# project_pankov_1_power_supply.net
KiCad netlist of a schematic drawn in Altium Designer
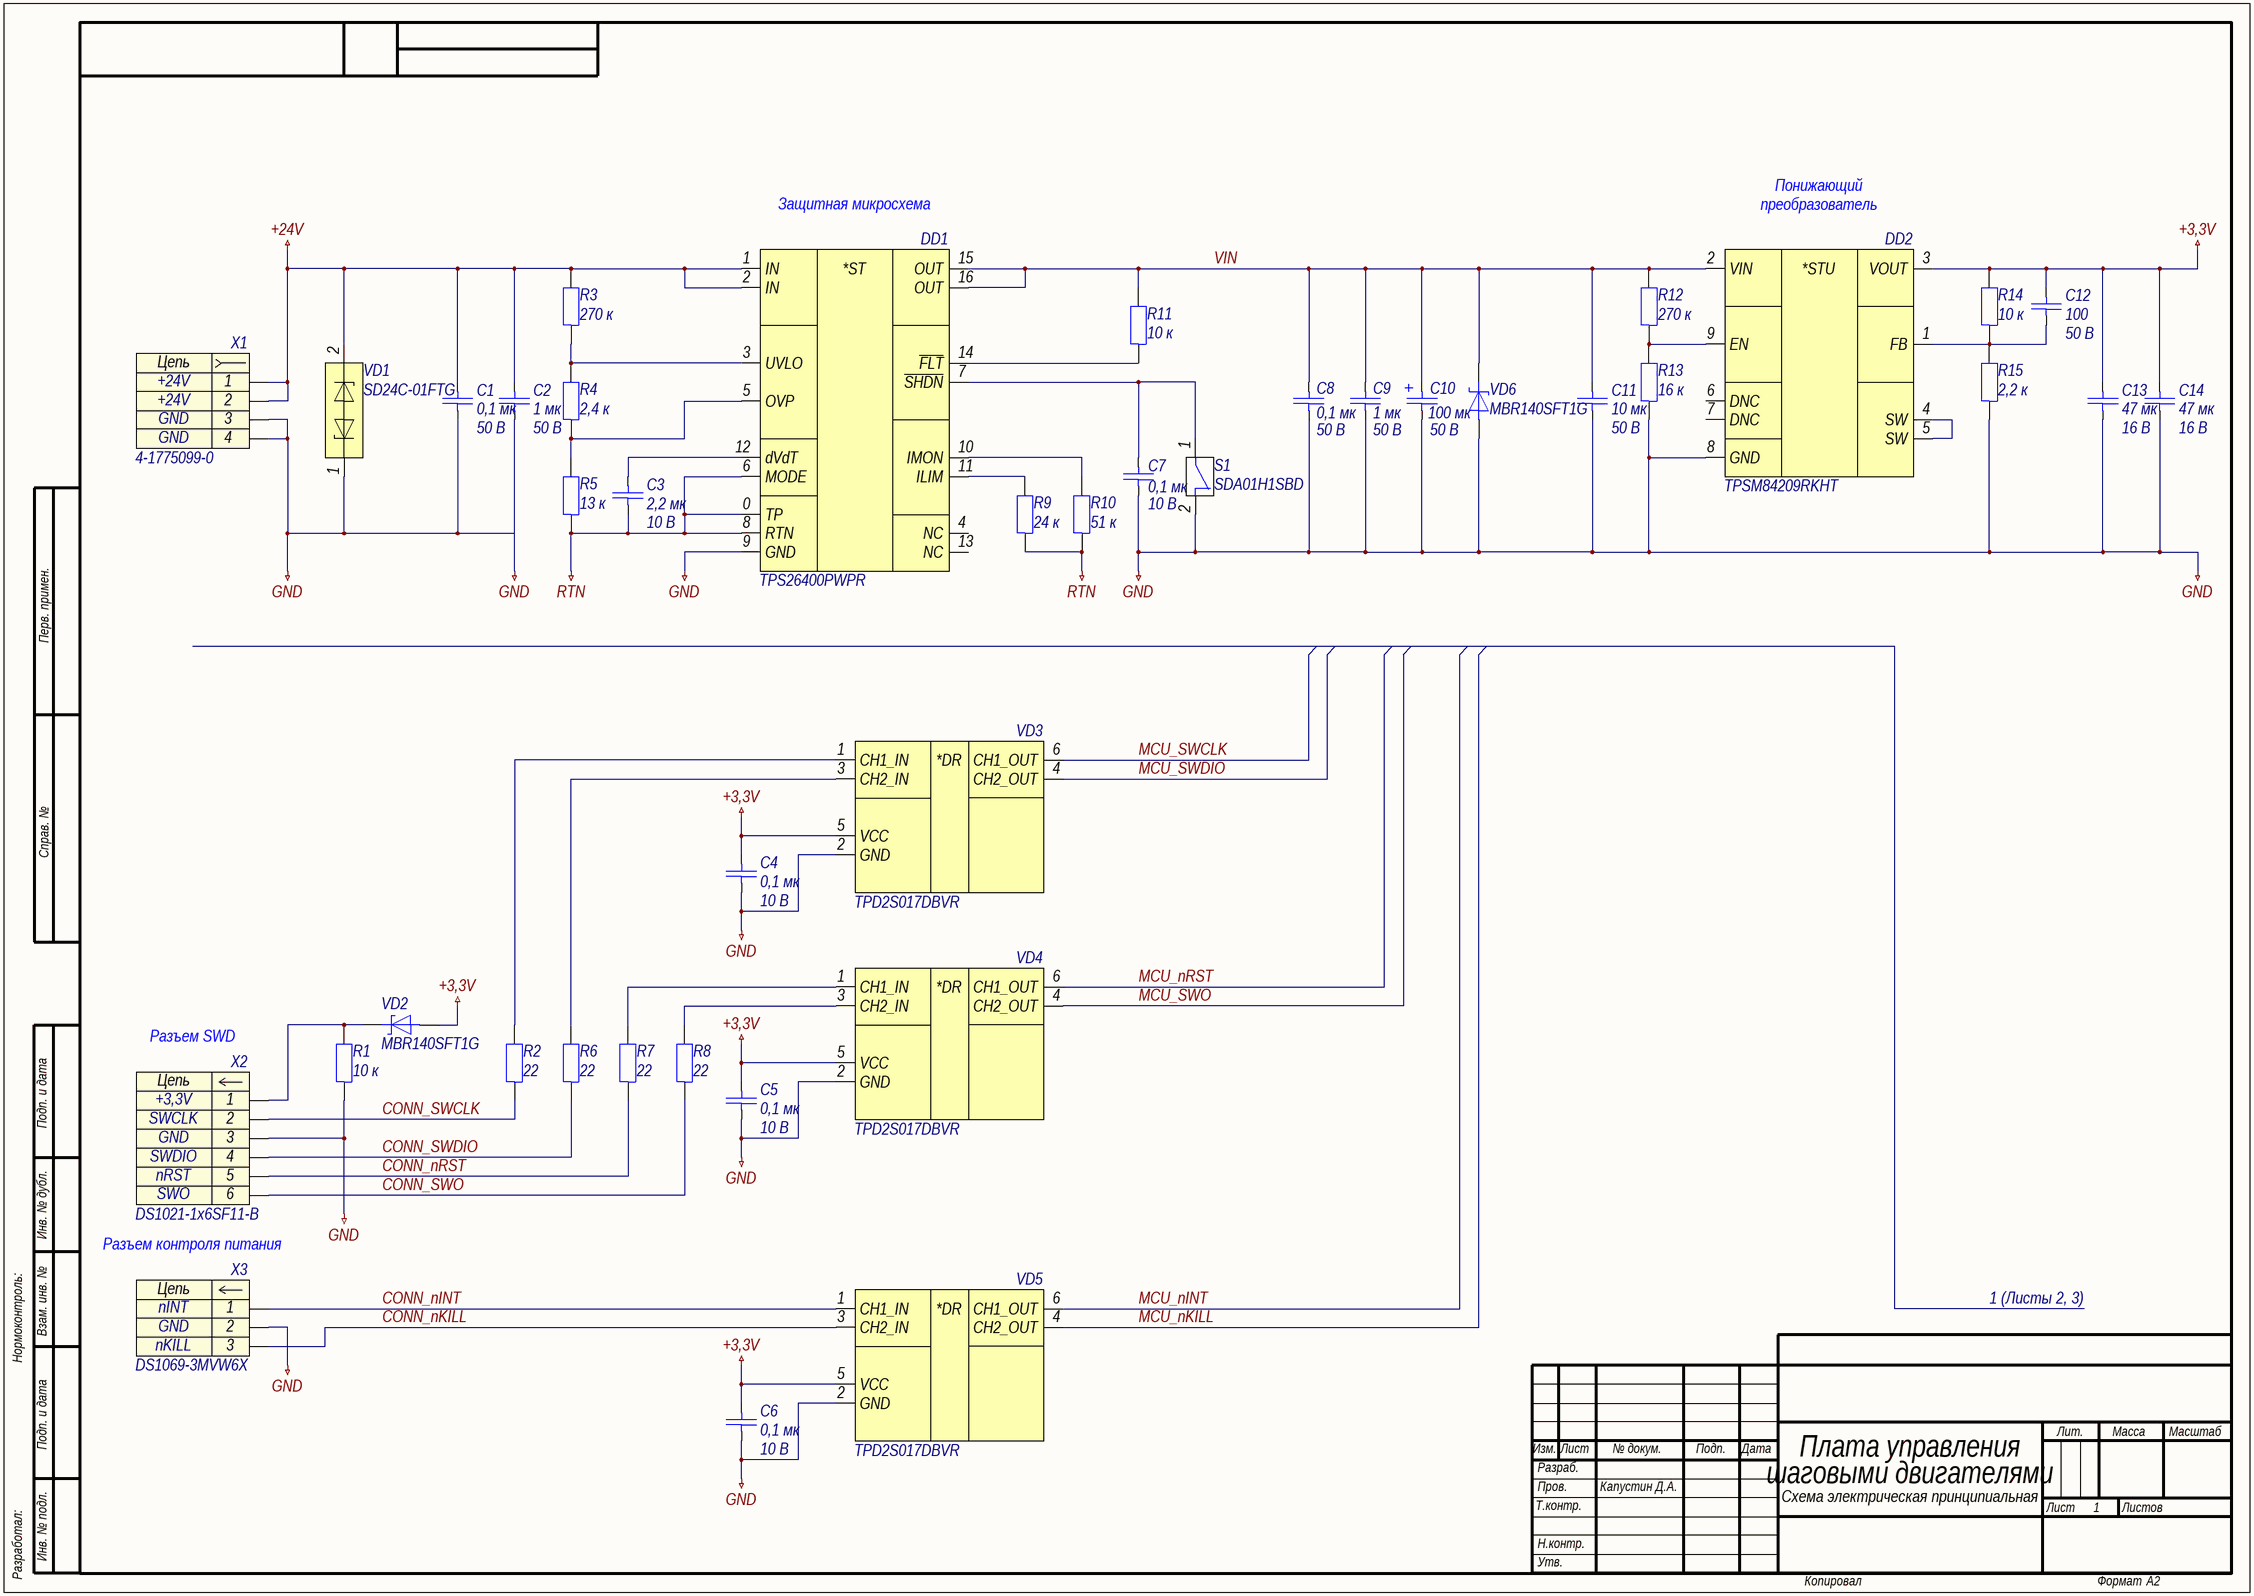
[diagram p0: project_pankov_1_power_supply.SchDoc]

(export (version "E")
  (design (tool "Eeschema 10.0.6"))
  (components
    (comp (ref "C1")
      (value "0,1 мк")
      (footprint "C0603")
      (description "=Описание")
      (fields (field (name "НАПРЯЖЕНИЕ") "50 В"))
      (libsource (lib "Database_Students") (part "CAPACITOR-NONPOLAR"))
    )
    (comp (ref "C2")
      (value "1 мк")
      (footprint "C0603")
      (description "=Описание")
      (fields (field (name "НАПРЯЖЕНИЕ") "50 В"))
      (libsource (lib "Database_Students") (part "CAPACITOR-NONPOLAR"))
    )
    (comp (ref "C3")
      (value "2,2 мк")
      (footprint "C0603")
      (description "=Описание")
      (fields (field (name "НАПРЯЖЕНИЕ") "10 В"))
      (libsource (lib "Database_Students") (part "CAPACITOR-NONPOLAR"))
    )
    (comp (ref "C4")
      (value "0,1 мк")
      (footprint "C0603")
      (description "=Описание")
      (fields (field (name "НАПРЯЖЕНИЕ") "10 В"))
      (libsource (lib "Database_Students") (part "CAPACITOR-NONPOLAR"))
    )
    (comp (ref "C5")
      (value "0,1 мк")
      (footprint "C0603")
      (description "=Описание")
      (fields (field (name "НАПРЯЖЕНИЕ") "10 В"))
      (libsource (lib "Database_Students") (part "CAPACITOR-NONPOLAR"))
    )
    (comp (ref "C6")
      (value "0,1 мк")
      (footprint "C0603")
      (description "=Описание")
      (fields (field (name "НАПРЯЖЕНИЕ") "10 В"))
      (libsource (lib "Database_Students") (part "CAPACITOR-NONPOLAR"))
    )
    (comp (ref "C7")
      (value "0,1 мк")
      (footprint "C0603")
      (description "=Описание")
      (fields (field (name "НАПРЯЖЕНИЕ") "10 В"))
      (libsource (lib "Database_Students") (part "CAPACITOR-NONPOLAR"))
    )
    (comp (ref "C8")
      (value "0,1 мк")
      (footprint "C0603")
      (description "=Описание")
      (fields (field (name "НАПРЯЖЕНИЕ") "50 В"))
      (libsource (lib "Database_Students") (part "CAPACITOR-NONPOLAR"))
    )
    (comp (ref "C9")
      (value "1 мк")
      (footprint "C0603")
      (description "=Описание")
      (fields (field (name "НАПРЯЖЕНИЕ") "50 В"))
      (libsource (lib "Database_Students") (part "CAPACITOR-NONPOLAR"))
    )
    (comp (ref "C10")
      (value "100 мк")
      (footprint "CAPAE-660X660X800")
      (description "=Описание")
      (fields (field (name "НАПРЯЖЕНИЕ") "50 В"))
      (libsource (lib "Database_Students") (part "CAPACITOR-POLAR"))
    )
    (comp (ref "C11")
      (value "10 мк")
      (footprint "C1206")
      (description "=Описание")
      (fields (field (name "НАПРЯЖЕНИЕ") "50 В"))
      (libsource (lib "Database_Students") (part "CAPACITOR-NONPOLAR"))
    )
    (comp (ref "C12")
      (value "100")
      (footprint "C0603")
      (description "=Описание")
      (fields (field (name "НАПРЯЖЕНИЕ") "50 В"))
      (libsource (lib "Database_Students") (part "CAPACITOR-NONPOLAR"))
    )
    (comp (ref "C13")
      (value "47 мк")
      (footprint "C1206")
      (description "=Описание")
      (fields (field (name "НАПРЯЖЕНИЕ") "16 В"))
      (libsource (lib "Database_Students") (part "CAPACITOR-NONPOLAR"))
    )
    (comp (ref "C14")
      (value "47 мк")
      (footprint "C1206")
      (description "=Описание")
      (fields (field (name "НАПРЯЖЕНИЕ") "16 В"))
      (libsource (lib "Database_Students") (part "CAPACITOR-NONPOLAR"))
    )
    (comp (ref "DD1")
      (value "TPS26400PWPR")
      (footprint "HTSSOP-16-P65-500X440X120-L63X25-T246X266")
      (description "=Описание")
      (libsource (lib "Database_Students") (part "TPS26400PWPR"))
    )
    (comp (ref "DD2")
      (value "TPSM84209RKHT")
      (footprint "QFN-FCMOD-9-P65-450X400X210")
      (description "=Описание")
      (libsource (lib "Database_Students") (part "TPSM84209RKHT"))
    )
    (comp (ref "R1")
      (value "10 к")
      (footprint "R0603")
      (description "=Описание")
      (libsource (lib "Database_Students") (part "RESISTOR-COMMON"))
    )
    (comp (ref "R2")
      (value "22")
      (footprint "R0603")
      (description "=Описание")
      (libsource (lib "Database_Students") (part "RESISTOR-COMMON"))
    )
    (comp (ref "R3")
      (value "270 к")
      (footprint "R0603")
      (description "=Описание")
      (libsource (lib "Database_Students") (part "RESISTOR-COMMON"))
    )
    (comp (ref "R4")
      (value "2,4 к")
      (footprint "R0603")
      (description "=Описание")
      (libsource (lib "Database_Students") (part "RESISTOR-COMMON"))
    )
    (comp (ref "R5")
      (value "13 к")
      (footprint "R0603")
      (description "=Описание")
      (libsource (lib "Database_Students") (part "RESISTOR-COMMON"))
    )
    (comp (ref "R6")
      (value "22")
      (footprint "R0603")
      (description "=Описание")
      (libsource (lib "Database_Students") (part "RESISTOR-COMMON"))
    )
    (comp (ref "R7")
      (value "22")
      (footprint "R0603")
      (description "=Описание")
      (libsource (lib "Database_Students") (part "RESISTOR-COMMON"))
    )
    (comp (ref "R8")
      (value "22")
      (footprint "R0603")
      (description "=Описание")
      (libsource (lib "Database_Students") (part "RESISTOR-COMMON"))
    )
    (comp (ref "R9")
      (value "24 к")
      (footprint "R0603")
      (description "=Описание")
      (libsource (lib "Database_Students") (part "RESISTOR-COMMON"))
    )
    (comp (ref "R10")
      (value "51 к")
      (footprint "R0603")
      (description "=Описание")
      (libsource (lib "Database_Students") (part "RESISTOR-COMMON"))
    )
    (comp (ref "R11")
      (value "10 к")
      (footprint "R0603")
      (description "=Описание")
      (libsource (lib "Database_Students") (part "RESISTOR-COMMON"))
    )
    (comp (ref "R12")
      (value "270 к")
      (footprint "R0603")
      (description "=Описание")
      (libsource (lib "Database_Students") (part "RESISTOR-COMMON"))
    )
    (comp (ref "R13")
      (value "16 к")
      (footprint "R0603")
      (description "=Описание")
      (libsource (lib "Database_Students") (part "RESISTOR-COMMON"))
    )
    (comp (ref "R14")
      (value "10 к")
      (footprint "R0603")
      (description "=Описание")
      (libsource (lib "Database_Students") (part "RESISTOR-COMMON"))
    )
    (comp (ref "R15")
      (value "2,2 к")
      (footprint "R0603")
      (description "=Описание")
      (libsource (lib "Database_Students") (part "RESISTOR-COMMON"))
    )
    (comp (ref "S1")
      (value "SDA01H1SBD")
      (footprint "SDA01H1SBD")
      (description "=Описание")
      (libsource (lib "Database_Students") (part "SWITCH-2C"))
    )
    (comp (ref "VD1")
      (value "SD24C-01FTG")
      (footprint "SOD-323-257X130X114")
      (description "=Описание")
      (libsource (lib "Database_Students") (part "ZENER-BI-DIRECTIONAL"))
    )
    (comp (ref "VD2")
      (value "MBR140SFT1G")
      (footprint "SOD-123FL-370X165X98")
      (description "=Описание")
      (libsource (lib "Database_Students") (part "DIODE-SCHOTTKY"))
    )
    (comp (ref "VD3")
      (value "TPD2S017DBVR")
      (footprint "SOT-23-6-P95-290X280X145")
      (description "=Описание")
      (libsource (lib "Database_Students") (part "TPD2S017DBVR"))
    )
    (comp (ref "VD4")
      (value "TPD2S017DBVR")
      (footprint "SOT-23-6-P95-290X280X145")
      (description "=Описание")
      (libsource (lib "Database_Students") (part "TPD2S017DBVR"))
    )
    (comp (ref "VD5")
      (value "TPD2S017DBVR")
      (footprint "SOT-23-6-P95-290X280X145")
      (description "=Описание")
      (libsource (lib "Database_Students") (part "TPD2S017DBVR"))
    )
    (comp (ref "VD6")
      (value "MBR140SFT1G")
      (footprint "SOD-123FL-370X165X98")
      (description "=Описание")
      (libsource (lib "Database_Students") (part "DIODE-SCHOTTKY"))
    )
    (comp (ref "X1")
      (value "4-1775099-0")
      (footprint "4-1775099-0")
      (description "=Описание")
      (libsource (lib "Database_Students") (part "HEADER-4-SCT"))
    )
    (comp (ref "X2")
      (value "DS1021-1x6SF11-B")
      (footprint "DS1021-1X6SF11-B")
      (description "=Описание")
      (libsource (lib "Database_Students") (part "HEADER-6-PLG"))
    )
    (comp (ref "X3")
      (value "DS1069-3MVW6X")
      (footprint "DS1069-3MVW6X")
      (description "=Описание")
      (libsource (lib "Database_Students") (part "HEADER-3-PLG"))
    )
  )
  (nets
    (net (code "1") (name "+3,3V") (class "Default")
      (node (ref "C12") (pin "1") (pinfunction "1_1") (pintype "passive"))
      (node (ref "C13") (pin "1") (pinfunction "1_1") (pintype "passive"))
      (node (ref "C14") (pin "1") (pinfunction "1_1") (pintype "passive"))
      (node (ref "C4") (pin "1") (pinfunction "1_1") (pintype "passive"))
      (node (ref "C5") (pin "1") (pinfunction "1_1") (pintype "passive"))
      (node (ref "C6") (pin "1") (pinfunction "1_1") (pintype "passive"))
      (node (ref "DD2") (pin "3") (pinfunction "VOUT_3") (pintype "passive"))
      (node (ref "R14") (pin "2") (pinfunction "2_2") (pintype "passive"))
      (node (ref "VD2") (pin "2") (pinfunction "2_2") (pintype "passive"))
      (node (ref "VD3") (pin "5") (pinfunction "VCC_5") (pintype "passive"))
      (node (ref "VD4") (pin "5") (pinfunction "VCC_5") (pintype "passive"))
      (node (ref "VD5") (pin "5") (pinfunction "VCC_5") (pintype "passive"))
    )
    (net (code "2") (name "+24V") (class "Default")
      (node (ref "C1") (pin "1") (pinfunction "1_1") (pintype "passive"))
      (node (ref "C2") (pin "1") (pinfunction "1_1") (pintype "passive"))
      (node (ref "DD1") (pin "1") (pinfunction "IN_1") (pintype "passive"))
      (node (ref "DD1") (pin "2") (pinfunction "IN_2") (pintype "passive"))
      (node (ref "R3") (pin "2") (pinfunction "2_2") (pintype "passive"))
      (node (ref "VD1") (pin "2") (pinfunction "2_2") (pintype "passive"))
      (node (ref "X1") (pin "1") (pinfunction "1_1") (pintype "passive"))
      (node (ref "X1") (pin "2") (pinfunction "2_2") (pintype "passive"))
    )
    (net (code "3") (name "/CONN_SWCLK") (class "Default")
      (node (ref "R2") (pin "1") (pinfunction "1_1") (pintype "passive"))
      (node (ref "X2") (pin "2") (pinfunction "2_2") (pintype "passive"))
    )
    (net (code "4") (name "/CONN_SWDIO") (class "Default")
      (node (ref "R6") (pin "1") (pinfunction "1_1") (pintype "passive"))
      (node (ref "X2") (pin "4") (pinfunction "4_4") (pintype "passive"))
    )
    (net (code "5") (name "/CONN_SWO") (class "Default")
      (node (ref "R8") (pin "1") (pinfunction "1_1") (pintype "passive"))
      (node (ref "X2") (pin "6") (pinfunction "6_6") (pintype "passive"))
    )
    (net (code "6") (name "/CONN_nINT") (class "Default")
      (node (ref "VD5") (pin "1") (pinfunction "CH1_IN_1") (pintype "passive"))
      (node (ref "X3") (pin "1") (pinfunction "1_1") (pintype "passive"))
    )
    (net (code "7") (name "/CONN_nKILL") (class "Default")
      (node (ref "VD5") (pin "3") (pinfunction "CH2_IN_3") (pintype "passive"))
      (node (ref "X3") (pin "3") (pinfunction "3_3") (pintype "passive"))
    )
    (net (code "8") (name "/CONN_nRST") (class "Default")
      (node (ref "R7") (pin "1") (pinfunction "1_1") (pintype "passive"))
      (node (ref "X2") (pin "5") (pinfunction "5_5") (pintype "passive"))
    )
    (net (code "9") (name "/MCU_SWCLK") (class "Default")
      (node (ref "VD3") (pin "6") (pinfunction "CH1_OUT_6") (pintype "passive"))
    )
    (net (code "10") (name "/MCU_SWDIO") (class "Default")
      (node (ref "VD3") (pin "4") (pinfunction "CH2_OUT_4") (pintype "passive"))
    )
    (net (code "11") (name "/MCU_SWO") (class "Default")
      (node (ref "VD4") (pin "4") (pinfunction "CH2_OUT_4") (pintype "passive"))
    )
    (net (code "12") (name "/MCU_nINT") (class "Default")
      (node (ref "VD5") (pin "6") (pinfunction "CH1_OUT_6") (pintype "passive"))
    )
    (net (code "13") (name "/MCU_nKILL") (class "Default")
      (node (ref "VD5") (pin "4") (pinfunction "CH2_OUT_4") (pintype "passive"))
    )
    (net (code "14") (name "/MCU_nRST") (class "Default")
      (node (ref "VD4") (pin "6") (pinfunction "CH1_OUT_6") (pintype "passive"))
    )
    (net (code "15") (name "/VIN") (class "Default")
      (node (ref "C10") (pin "1") (pinfunction "1_1") (pintype "passive"))
      (node (ref "C11") (pin "1") (pinfunction "1_1") (pintype "passive"))
      (node (ref "C8") (pin "1") (pinfunction "1_1") (pintype "passive"))
      (node (ref "C9") (pin "1") (pinfunction "1_1") (pintype "passive"))
      (node (ref "DD1") (pin "15") (pinfunction "OUT_15") (pintype "passive"))
      (node (ref "DD1") (pin "16") (pinfunction "OUT_16") (pintype "passive"))
      (node (ref "DD2") (pin "2") (pinfunction "VIN_2") (pintype "passive"))
      (node (ref "R11") (pin "2") (pinfunction "2_2") (pintype "passive"))
      (node (ref "R12") (pin "2") (pinfunction "2_2") (pintype "passive"))
      (node (ref "VD6") (pin "1") (pinfunction "1_1") (pintype "passive"))
    )
    (net (code "16") (name "GND") (class "Default")
      (node (ref "C1") (pin "2") (pinfunction "2_2") (pintype "passive"))
      (node (ref "C10") (pin "2") (pinfunction "2_2") (pintype "passive"))
      (node (ref "C11") (pin "2") (pinfunction "2_2") (pintype "passive"))
      (node (ref "C13") (pin "2") (pinfunction "2_2") (pintype "passive"))
      (node (ref "C14") (pin "2") (pinfunction "2_2") (pintype "passive"))
      (node (ref "C2") (pin "2") (pinfunction "2_2") (pintype "passive"))
      (node (ref "C4") (pin "2") (pinfunction "2_2") (pintype "passive"))
      (node (ref "C5") (pin "2") (pinfunction "2_2") (pintype "passive"))
      (node (ref "C6") (pin "2") (pinfunction "2_2") (pintype "passive"))
      (node (ref "C7") (pin "2") (pinfunction "2_2") (pintype "passive"))
      (node (ref "C8") (pin "2") (pinfunction "2_2") (pintype "passive"))
      (node (ref "C9") (pin "2") (pinfunction "2_2") (pintype "passive"))
      (node (ref "DD1") (pin "9") (pinfunction "GND_9") (pintype "passive"))
      (node (ref "DD2") (pin "8") (pinfunction "GND_8") (pintype "passive"))
      (node (ref "R1") (pin "1") (pinfunction "1_1") (pintype "passive"))
      (node (ref "R13") (pin "1") (pinfunction "1_1") (pintype "passive"))
      (node (ref "R15") (pin "1") (pinfunction "1_1") (pintype "passive"))
      (node (ref "S1") (pin "2") (pinfunction "2_2") (pintype "passive"))
      (node (ref "VD1") (pin "1") (pinfunction "1_1") (pintype "passive"))
      (node (ref "VD3") (pin "2") (pinfunction "GND_2") (pintype "passive"))
      (node (ref "VD4") (pin "2") (pinfunction "GND_2") (pintype "passive"))
      (node (ref "VD5") (pin "2") (pinfunction "GND_2") (pintype "passive"))
      (node (ref "VD6") (pin "2") (pinfunction "2_2") (pintype "passive"))
      (node (ref "X1") (pin "3") (pinfunction "3_3") (pintype "passive"))
      (node (ref "X1") (pin "4") (pinfunction "4_4") (pintype "passive"))
      (node (ref "X2") (pin "3") (pinfunction "3_3") (pintype "passive"))
      (node (ref "X3") (pin "2") (pinfunction "2_2") (pintype "passive"))
    )
    (net (code "17") (name "Net-(DD1-ILIM)") (class "Default")
      (node (ref "DD1") (pin "11") (pinfunction "ILIM_11") (pintype "passive"))
      (node (ref "R9") (pin "2") (pinfunction "2_2") (pintype "passive"))
    )
    (net (code "18") (name "Net-(DD1-IMON)") (class "Default")
      (node (ref "DD1") (pin "10") (pinfunction "IMON_10") (pintype "passive"))
      (node (ref "R10") (pin "2") (pinfunction "2_2") (pintype "passive"))
    )
    (net (code "19") (name "Net-(DD1-OVP)") (class "Default")
      (node (ref "DD1") (pin "5") (pinfunction "OVP_5") (pintype "passive"))
      (node (ref "R4") (pin "1") (pinfunction "1_1") (pintype "passive"))
      (node (ref "R5") (pin "2") (pinfunction "2_2") (pintype "passive"))
    )
    (net (code "20") (name "Net-(DD1-UVLO)") (class "Default")
      (node (ref "DD1") (pin "3") (pinfunction "UVLO_3") (pintype "passive"))
      (node (ref "R3") (pin "1") (pinfunction "1_1") (pintype "passive"))
      (node (ref "R4") (pin "2") (pinfunction "2_2") (pintype "passive"))
    )
    (net (code "21") (name "Net-(DD1-dVdT)") (class "Default")
      (node (ref "C3") (pin "1") (pinfunction "1_1") (pintype "passive"))
      (node (ref "DD1") (pin "12") (pinfunction "dVdT_12") (pintype "passive"))
    )
    (net (code "22") (name "Net-(DD1-~{FLT})") (class "Default")
      (node (ref "DD1") (pin "14") (pinfunction "~{FLT}_14") (pintype "passive"))
      (node (ref "R11") (pin "1") (pinfunction "1_1") (pintype "passive"))
    )
    (net (code "23") (name "Net-(DD1-~{SHDN})") (class "Default")
      (node (ref "C7") (pin "1") (pinfunction "1_1") (pintype "passive"))
      (node (ref "DD1") (pin "7") (pinfunction "~{SHDN}_7") (pintype "passive"))
      (node (ref "S1") (pin "1") (pinfunction "1_1") (pintype "passive"))
    )
    (net (code "24") (name "Net-(DD2-EN)") (class "Default")
      (node (ref "DD2") (pin "9") (pinfunction "EN_9") (pintype "passive"))
      (node (ref "R12") (pin "1") (pinfunction "1_1") (pintype "passive"))
      (node (ref "R13") (pin "2") (pinfunction "2_2") (pintype "passive"))
    )
    (net (code "25") (name "Net-(DD2-FB)") (class "Default")
      (node (ref "C12") (pin "2") (pinfunction "2_2") (pintype "passive"))
      (node (ref "DD2") (pin "1") (pinfunction "FB_1") (pintype "passive"))
      (node (ref "R14") (pin "1") (pinfunction "1_1") (pintype "passive"))
      (node (ref "R15") (pin "2") (pinfunction "2_2") (pintype "passive"))
    )
    (net (code "26") (name "Net-(DD2-SW-Pad4)") (class "Default")
      (node (ref "DD2") (pin "4") (pinfunction "SW_4") (pintype "passive"))
      (node (ref "DD2") (pin "5") (pinfunction "SW_5") (pintype "passive"))
    )
    (net (code "27") (name "Net-(R1-Pad2)") (class "Default")
      (node (ref "R1") (pin "2") (pinfunction "2_2") (pintype "passive"))
      (node (ref "VD2") (pin "1") (pinfunction "1_1") (pintype "passive"))
      (node (ref "X2") (pin "1") (pinfunction "1_1") (pintype "passive"))
    )
    (net (code "28") (name "Net-(VD3-CH1_IN)") (class "Default")
      (node (ref "R2") (pin "2") (pinfunction "2_2") (pintype "passive"))
      (node (ref "VD3") (pin "1") (pinfunction "CH1_IN_1") (pintype "passive"))
    )
    (net (code "29") (name "Net-(VD3-CH2_IN)") (class "Default")
      (node (ref "R6") (pin "2") (pinfunction "2_2") (pintype "passive"))
      (node (ref "VD3") (pin "3") (pinfunction "CH2_IN_3") (pintype "passive"))
    )
    (net (code "30") (name "Net-(VD4-CH1_IN)") (class "Default")
      (node (ref "R7") (pin "2") (pinfunction "2_2") (pintype "passive"))
      (node (ref "VD4") (pin "1") (pinfunction "CH1_IN_1") (pintype "passive"))
    )
    (net (code "31") (name "Net-(VD4-CH2_IN)") (class "Default")
      (node (ref "R8") (pin "2") (pinfunction "2_2") (pintype "passive"))
      (node (ref "VD4") (pin "3") (pinfunction "CH2_IN_3") (pintype "passive"))
    )
    (net (code "32") (name "RTN") (class "Default")
      (node (ref "C3") (pin "2") (pinfunction "2_2") (pintype "passive"))
      (node (ref "DD1") (pin "0") (pinfunction "TP_0") (pintype "passive"))
      (node (ref "DD1") (pin "6") (pinfunction "MODE_6") (pintype "passive"))
      (node (ref "DD1") (pin "8") (pinfunction "RTN_8") (pintype "passive"))
      (node (ref "R10") (pin "1") (pinfunction "1_1") (pintype "passive"))
      (node (ref "R5") (pin "1") (pinfunction "1_1") (pintype "passive"))
      (node (ref "R9") (pin "1") (pinfunction "1_1") (pintype "passive"))
    )
    (net (code "33") (name "unconnected-(DD1-NC-Pad4)") (class "Default")
      (node (ref "DD1") (pin "4") (pinfunction "NC_4") (pintype "passive"))
    )
    (net (code "34") (name "unconnected-(DD1-NC-Pad13)") (class "Default")
      (node (ref "DD1") (pin "13") (pinfunction "NC_13") (pintype "passive"))
    )
    (net (code "35") (name "unconnected-(DD2-DNC-Pad6)") (class "Default")
      (node (ref "DD2") (pin "6") (pinfunction "DNC_6") (pintype "passive"))
    )
    (net (code "36") (name "unconnected-(DD2-DNC-Pad7)") (class "Default")
      (node (ref "DD2") (pin "7") (pinfunction "DNC_7") (pintype "passive"))
    )
  )
)
